# BCMv4.net
KiCad netlist of a schematic drawn in EAGLE
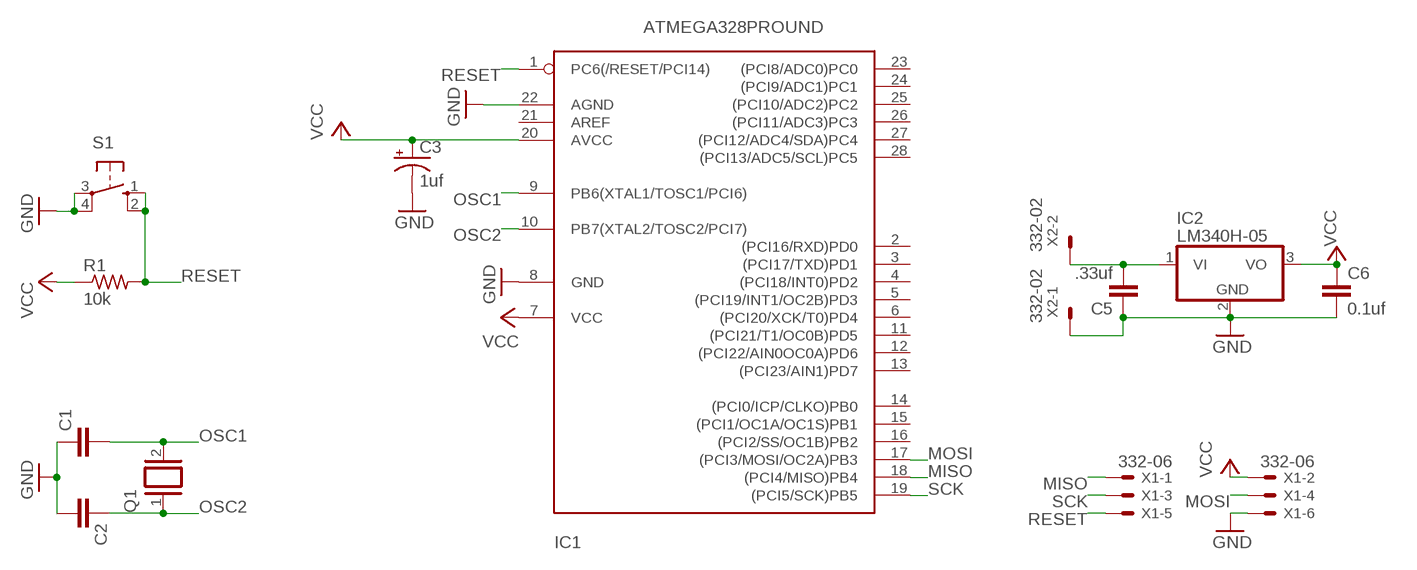
[diagram p0: schematic, sheet 1]

(export (version "E")
  (design (tool "Eeschema 10.0.6"))
  (components
    (comp (ref "C1")
      (value "C2,5-3")
      (footprint "eagle-import:C2.5-3")
      (libsource (lib "eagle-import") (part "C2,5-3"))
    )
    (comp (ref "C2")
      (value "C2,5-3")
      (footprint "eagle-import:C2.5-3")
      (libsource (lib "eagle-import") (part "C2,5-3"))
    )
    (comp (ref "C3")
      (value "1uf")
      (footprint "eagle-import:E2,5-6")
      (libsource (lib "eagle-import") (part "CPOL-USE2.5-6"))
    )
    (comp (ref "C5")
      (value ".33uf")
      (footprint "eagle-import:C2.5-3")
      (libsource (lib "eagle-import") (part "C2,5-3"))
    )
    (comp (ref "C6")
      (value "0.1uf")
      (footprint "eagle-import:C2.5-3")
      (libsource (lib "eagle-import") (part "C2,5-3"))
    )
    (comp (ref "IC1")
      (value "ATMEGA328PROUND")
      (footprint "eagle-import:DIL28-3-ROUND")
      (libsource (lib "eagle-import") (part "ATMEGA328PROUND"))
    )
    (comp (ref "IC2")
      (value "LM340H-05")
      (footprint "eagle-import:TO220H")
      (libsource (lib "eagle-import") (part "LM340?-H05"))
    )
    (comp (ref "Q1")
      (value "XTAL/S")
      (footprint "eagle-import:QS")
      (libsource (lib "eagle-import") (part "XTAL/S"))
    )
    (comp (ref "R1")
      (value "10k")
      (footprint "eagle-import:0204_7")
      (libsource (lib "eagle-import") (part "R-US_0204/7"))
    )
    (comp (ref "S1")
      (value "10-XX")
      (footprint "eagle-import:B3F-10XX")
      (fields (field (name "MPN") "B3F-1000"))
      (libsource (lib "eagle-import") (part "10-XX"))
    )
    (comp (ref "X1")
      (value "332-06")
      (footprint "eagle-import:332-06")
      (libsource (lib "eagle-import") (part "332-06"))
    )
    (comp (ref "X2")
      (value "332-02")
      (footprint "eagle-import:332-02")
      (libsource (lib "eagle-import") (part "332-02"))
    )
  )
  (nets
    (net (code "1") (name "/MISO") (class "Default")
      (node (ref "IC1") (pin "18") (pinfunction "(PCI4/MISO)PB4_18") (pintype "bidirectional"))
      (node (ref "X1") (pin "1") (pinfunction "S_1") (pintype "passive"))
    )
    (net (code "2") (name "/MOSI") (class "Default")
      (node (ref "IC1") (pin "17") (pinfunction "(PCI3/MOSI/OC2A)PB3_17") (pintype "bidirectional"))
      (node (ref "X1") (pin "4") (pinfunction "S_4") (pintype "passive"))
    )
    (net (code "3") (name "/OSC1") (class "Default")
      (node (ref "C1") (pin "2") (pinfunction "2_2") (pintype "passive"))
      (node (ref "IC1") (pin "9") (pinfunction "PB6(XTAL1/TOSC1/PCI6)_9") (pintype "bidirectional"))
      (node (ref "Q1") (pin "2") (pinfunction "2_2") (pintype "passive"))
    )
    (net (code "4") (name "/OSC2") (class "Default")
      (node (ref "C2") (pin "1") (pinfunction "1_1") (pintype "passive"))
      (node (ref "IC1") (pin "10") (pinfunction "PB7(XTAL2/TOSC2/PCI7)_10") (pintype "bidirectional"))
      (node (ref "Q1") (pin "1") (pinfunction "1_1") (pintype "passive"))
    )
    (net (code "5") (name "/RESET") (class "Default")
      (node (ref "IC1") (pin "1") (pinfunction "PC6(/RESET/PCI14)_1") (pintype "bidirectional"))
      (node (ref "R1") (pin "2") (pinfunction "2_2") (pintype "passive"))
      (node (ref "S1") (pin "1") (pinfunction "S_1") (pintype "passive"))
      (node (ref "S1") (pin "2") (pinfunction "S1_2") (pintype "passive"))
      (node (ref "X1") (pin "5") (pinfunction "S_5") (pintype "passive"))
    )
    (net (code "6") (name "/SCK") (class "Default")
      (node (ref "IC1") (pin "19") (pinfunction "(PCI5/SCK)PB5_19") (pintype "bidirectional"))
      (node (ref "X1") (pin "3") (pinfunction "S_3") (pintype "passive"))
    )
    (net (code "7") (name "GND") (class "Default")
      (node (ref "C1") (pin "1") (pinfunction "1_1") (pintype "passive"))
      (node (ref "C2") (pin "2") (pinfunction "2_2") (pintype "passive"))
      (node (ref "C3") (pin "-") (pinfunction "-_-") (pintype "passive"))
      (node (ref "C5") (pin "1") (pinfunction "1_1") (pintype "passive"))
      (node (ref "C6") (pin "2") (pinfunction "2_2") (pintype "passive"))
      (node (ref "IC1") (pin "22") (pinfunction "AGND_22") (pintype "bidirectional"))
      (node (ref "IC1") (pin "8") (pinfunction "GND_8") (pintype "bidirectional"))
      (node (ref "IC2") (pin "2") (pinfunction "GND_2") (pintype "passive"))
      (node (ref "S1") (pin "3") (pinfunction "P_3") (pintype "passive"))
      (node (ref "S1") (pin "4") (pinfunction "P1_4") (pintype "passive"))
      (node (ref "X1") (pin "6") (pinfunction "S_6") (pintype "passive"))
      (node (ref "X2") (pin "1") (pinfunction "S_1") (pintype "passive"))
    )
    (net (code "8") (name "Net-(IC2-VI)") (class "Default")
      (node (ref "C5") (pin "2") (pinfunction "2_2") (pintype "passive"))
      (node (ref "IC2") (pin "1") (pinfunction "VI_1") (pintype "input"))
      (node (ref "X2") (pin "2") (pinfunction "S_2") (pintype "passive"))
    )
    (net (code "9") (name "VCC") (class "Default")
      (node (ref "C3") (pin "+") (pinfunction "+_+") (pintype "passive"))
      (node (ref "C6") (pin "1") (pinfunction "1_1") (pintype "passive"))
      (node (ref "IC1") (pin "20") (pinfunction "AVCC_20") (pintype "bidirectional"))
      (node (ref "IC1") (pin "7") (pinfunction "VCC_7") (pintype "bidirectional"))
      (node (ref "IC2") (pin "3") (pinfunction "VO_3") (pintype "passive"))
      (node (ref "R1") (pin "1") (pinfunction "1_1") (pintype "passive"))
      (node (ref "X1") (pin "2") (pinfunction "S_2") (pintype "passive"))
    )
    (net (code "10") (name "unconnected-(IC1-(PCI0{slash}ICP{slash}CLKO)PB0-Pad14)") (class "Default")
      (node (ref "IC1") (pin "14") (pinfunction "(PCI0/ICP/CLKO)PB0_14") (pintype "bidirectional"))
    )
    (net (code "11") (name "unconnected-(IC1-(PCI1{slash}OC1A{slash}OC1S)PB1-Pad15)") (class "Default")
      (node (ref "IC1") (pin "15") (pinfunction "(PCI1/OC1A/OC1S)PB1_15") (pintype "bidirectional"))
    )
    (net (code "12") (name "unconnected-(IC1-(PCI2{slash}SS{slash}OC1B)PB2-Pad16)") (class "Default")
      (node (ref "IC1") (pin "16") (pinfunction "(PCI2/SS/OC1B)PB2_16") (pintype "bidirectional"))
    )
    (net (code "13") (name "unconnected-(IC1-(PCI8{slash}ADC0)PC0-Pad23)") (class "Default")
      (node (ref "IC1") (pin "23") (pinfunction "(PCI8/ADC0)PC0_23") (pintype "bidirectional"))
    )
    (net (code "14") (name "unconnected-(IC1-(PCI9{slash}ADC1)PC1-Pad24)") (class "Default")
      (node (ref "IC1") (pin "24") (pinfunction "(PCI9/ADC1)PC1_24") (pintype "bidirectional"))
    )
    (net (code "15") (name "unconnected-(IC1-(PCI10{slash}ADC2)PC2-Pad25)") (class "Default")
      (node (ref "IC1") (pin "25") (pinfunction "(PCI10/ADC2)PC2_25") (pintype "bidirectional"))
    )
    (net (code "16") (name "unconnected-(IC1-(PCI11{slash}ADC3)PC3-Pad26)") (class "Default")
      (node (ref "IC1") (pin "26") (pinfunction "(PCI11/ADC3)PC3_26") (pintype "bidirectional"))
    )
    (net (code "17") (name "unconnected-(IC1-(PCI12{slash}ADC4{slash}SDA)PC4-Pad27)") (class "Default")
      (node (ref "IC1") (pin "27") (pinfunction "(PCI12/ADC4/SDA)PC4_27") (pintype "bidirectional"))
    )
    (net (code "18") (name "unconnected-(IC1-(PCI13{slash}ADC5{slash}SCL)PC5-Pad28)") (class "Default")
      (node (ref "IC1") (pin "28") (pinfunction "(PCI13/ADC5/SCL)PC5_28") (pintype "bidirectional"))
    )
    (net (code "19") (name "unconnected-(IC1-(PCI16{slash}RXD)PD0-Pad2)") (class "Default")
      (node (ref "IC1") (pin "2") (pinfunction "(PCI16/RXD)PD0_2") (pintype "bidirectional"))
    )
    (net (code "20") (name "unconnected-(IC1-(PCI17{slash}TXD)PD1-Pad3)") (class "Default")
      (node (ref "IC1") (pin "3") (pinfunction "(PCI17/TXD)PD1_3") (pintype "bidirectional"))
    )
    (net (code "21") (name "unconnected-(IC1-(PCI18{slash}INT0)PD2-Pad4)") (class "Default")
      (node (ref "IC1") (pin "4") (pinfunction "(PCI18/INT0)PD2_4") (pintype "bidirectional"))
    )
    (net (code "22") (name "unconnected-(IC1-(PCI19{slash}INT1{slash}OC2B)PD3-Pad5)") (class "Default")
      (node (ref "IC1") (pin "5") (pinfunction "(PCI19/INT1/OC2B)PD3_5") (pintype "bidirectional"))
    )
    (net (code "23") (name "unconnected-(IC1-(PCI20{slash}XCK{slash}T0)PD4-Pad6)") (class "Default")
      (node (ref "IC1") (pin "6") (pinfunction "(PCI20/XCK/T0)PD4_6") (pintype "bidirectional"))
    )
    (net (code "24") (name "unconnected-(IC1-(PCI21{slash}T1{slash}OC0B)PD5-Pad11)") (class "Default")
      (node (ref "IC1") (pin "11") (pinfunction "(PCI21/T1/OC0B)PD5_11") (pintype "bidirectional"))
    )
    (net (code "25") (name "unconnected-(IC1-(PCI22{slash}AIN0OC0A)PD6-Pad12)") (class "Default")
      (node (ref "IC1") (pin "12") (pinfunction "(PCI22/AIN0OC0A)PD6_12") (pintype "bidirectional"))
    )
    (net (code "26") (name "unconnected-(IC1-(PCI23{slash}AIN1)PD7-Pad13)") (class "Default")
      (node (ref "IC1") (pin "13") (pinfunction "(PCI23/AIN1)PD7_13") (pintype "bidirectional"))
    )
    (net (code "27") (name "unconnected-(IC1-AREF-Pad21)") (class "Default")
      (node (ref "IC1") (pin "21") (pinfunction "AREF_21") (pintype "bidirectional"))
    )
  )
)
